# DisplayPort_Mux.net
KiCad netlist of a schematic drawn in Altium Designer
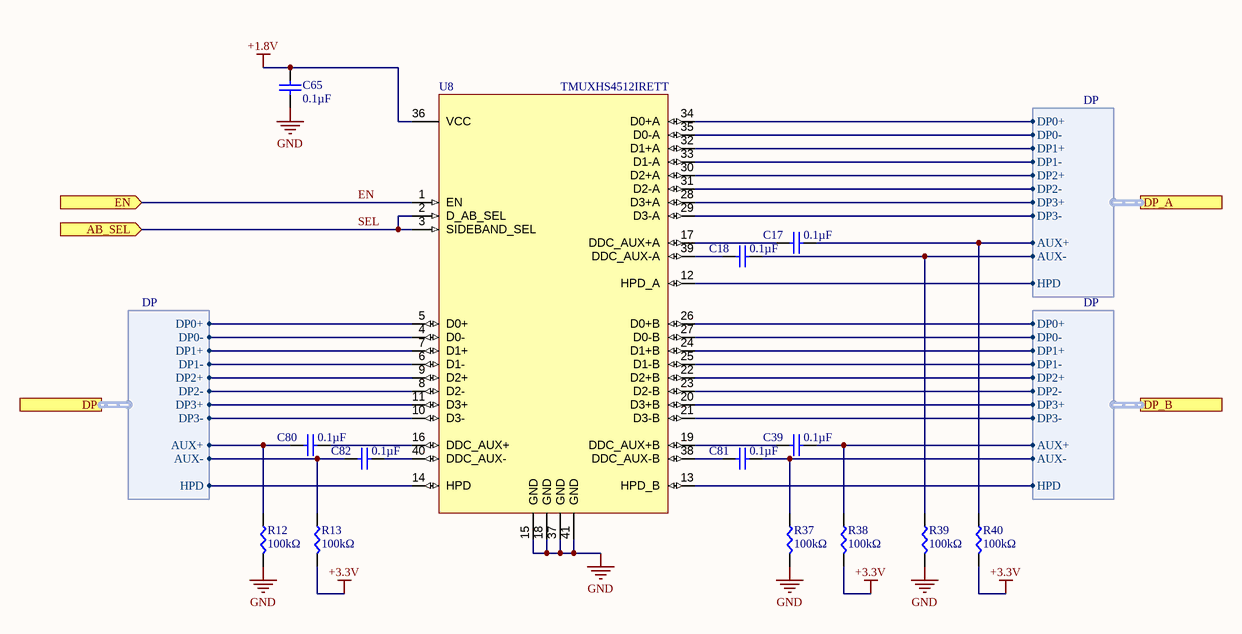
[diagram p0: DisplayPort_Mux.SchDoc]

(export (version "E")
  (design (tool "Eeschema 10.0.6"))
  (components
    (comp (ref "C17")
      (value "0.1µF")
      (footprint "CAP0402")
      (description "0.1 µF ±10% 50V Ceramic Capacitor X5R 0402 (1005 Metric)")
      (fields (field (name "VOLTAGE") "50V") (field (name "Comment") "CC0402KRX5R9BB104"))
      (libsource (lib "Schlib1") (part "CC0402KRX5R9BB104"))
    )
    (comp (ref "C18")
      (value "0.1µF")
      (footprint "CAP0402")
      (description "0.1 µF ±10% 50V Ceramic Capacitor X5R 0402 (1005 Metric)")
      (fields (field (name "VOLTAGE") "50V") (field (name "Comment") "CC0402KRX5R9BB104"))
      (libsource (lib "Schlib1") (part "CC0402KRX5R9BB104"))
    )
    (comp (ref "C39")
      (value "0.1µF")
      (footprint "CAP0402")
      (description "0.1 µF ±10% 50V Ceramic Capacitor X5R 0402 (1005 Metric)")
      (fields (field (name "VOLTAGE") "50V") (field (name "Comment") "CC0402KRX5R9BB104"))
      (libsource (lib "Schlib1") (part "CC0402KRX5R9BB104"))
    )
    (comp (ref "C65")
      (value "0.1µF")
      (footprint "CAP0402")
      (description "0.1 µF ±10% 50V Ceramic Capacitor X5R 0402 (1005 Metric)")
      (fields (field (name "VOLTAGE") "50V") (field (name "Comment") "CC0402KRX5R9BB104"))
      (libsource (lib "Schlib1") (part "CC0402KRX5R9BB104"))
    )
    (comp (ref "C80")
      (value "0.1µF")
      (footprint "CAP0402")
      (description "0.1 µF ±10% 50V Ceramic Capacitor X5R 0402 (1005 Metric)")
      (fields (field (name "VOLTAGE") "50V") (field (name "Comment") "CC0402KRX5R9BB104"))
      (libsource (lib "Schlib1") (part "CC0402KRX5R9BB104"))
    )
    (comp (ref "C81")
      (value "0.1µF")
      (footprint "CAP0402")
      (description "0.1 µF ±10% 50V Ceramic Capacitor X5R 0402 (1005 Metric)")
      (fields (field (name "VOLTAGE") "50V") (field (name "Comment") "CC0402KRX5R9BB104"))
      (libsource (lib "Schlib1") (part "CC0402KRX5R9BB104"))
    )
    (comp (ref "C82")
      (value "0.1µF")
      (footprint "CAP0402")
      (description "0.1 µF ±10% 50V Ceramic Capacitor X5R 0402 (1005 Metric)")
      (fields (field (name "VOLTAGE") "50V") (field (name "Comment") "CC0402KRX5R9BB104"))
      (libsource (lib "Schlib1") (part "CC0402KRX5R9BB104"))
    )
    (comp (ref "R12")
      (value "100kΩ")
      (footprint "RES0402")
      (description "100 kOhms ±1% 0.1W, 1/10W Chip Resistor 0402 (1005 Metric) Automotive AEC-Q200 Thick Film")
      (fields (field (name "Comment") "ERJ-2RKF1003X"))
      (libsource (lib "Schlib1") (part "ERJ-2RKF1003X"))
    )
    (comp (ref "R13")
      (value "100kΩ")
      (footprint "RES0402")
      (description "100 kOhms ±1% 0.1W, 1/10W Chip Resistor 0402 (1005 Metric) Automotive AEC-Q200 Thick Film")
      (fields (field (name "Comment") "ERJ-2RKF1003X"))
      (libsource (lib "Schlib1") (part "ERJ-2RKF1003X"))
    )
    (comp (ref "R37")
      (value "100kΩ")
      (footprint "RES0402")
      (description "100 kOhms ±1% 0.1W, 1/10W Chip Resistor 0402 (1005 Metric) Automotive AEC-Q200 Thick Film")
      (fields (field (name "Comment") "ERJ-2RKF1003X"))
      (libsource (lib "Schlib1") (part "ERJ-2RKF1003X"))
    )
    (comp (ref "R38")
      (value "100kΩ")
      (footprint "RES0402")
      (description "100 kOhms ±1% 0.1W, 1/10W Chip Resistor 0402 (1005 Metric) Automotive AEC-Q200 Thick Film")
      (fields (field (name "Comment") "ERJ-2RKF1003X"))
      (libsource (lib "Schlib1") (part "ERJ-2RKF1003X"))
    )
    (comp (ref "R39")
      (value "100kΩ")
      (footprint "RES0402")
      (description "100 kOhms ±1% 0.1W, 1/10W Chip Resistor 0402 (1005 Metric) Automotive AEC-Q200 Thick Film")
      (fields (field (name "Comment") "ERJ-2RKF1003X"))
      (libsource (lib "Schlib1") (part "ERJ-2RKF1003X"))
    )
    (comp (ref "R40")
      (value "100kΩ")
      (footprint "RES0402")
      (description "100 kOhms ±1% 0.1W, 1/10W Chip Resistor 0402 (1005 Metric) Automotive AEC-Q200 Thick Film")
      (fields (field (name "Comment") "ERJ-2RKF1003X"))
      (libsource (lib "Schlib1") (part "ERJ-2RKF1003X"))
    )
    (comp (ref "U8")
      (value "TMUXHS4512IRETT")
      (description "6 Circuit IC Switch 1:2, 2:1 160Ohm 40-WQFN (6x3)")
      (fields (field (name "MANUFACTURER") "Texas Instruments"))
      (libsource (lib "Schlib1") (part "TMUXHS4512IRETT"))
    )
  )
  (nets
    (net (code "2") (name "+1.8V") (class "Default")
      (node (ref "C65") (pin "2") (pinfunction "2_2") (pintype "passive"))
      (node (ref "U8") (pin "36") (pinfunction "VCC_36") (pintype "passive"))
    )
    (net (code "3") (name "+3.3V") (class "Default")
      (node (ref "R13") (pin "1") (pinfunction "1_1") (pintype "passive"))
      (node (ref "R38") (pin "1") (pinfunction "1_1") (pintype "passive"))
      (node (ref "R40") (pin "1") (pinfunction "1_1") (pintype "passive"))
    )
    (net (code "4") (name "/EN") (class "Default")
      (node (ref "U8") (pin "1") (pinfunction "EN_1") (pintype "input"))
    )
    (net (code "5") (name "/SEL") (class "Default")
      (node (ref "U8") (pin "2") (pinfunction "D_AB_SEL_2") (pintype "input"))
      (node (ref "U8") (pin "3") (pinfunction "SIDEBAND_SEL_3") (pintype "input"))
    )
    (net (code "7") (name "GND") (class "Default")
      (node (ref "C65") (pin "1") (pinfunction "1_1") (pintype "passive"))
      (node (ref "R12") (pin "1") (pinfunction "1_1") (pintype "passive"))
      (node (ref "R37") (pin "1") (pinfunction "1_1") (pintype "passive"))
      (node (ref "R39") (pin "1") (pinfunction "1_1") (pintype "passive"))
      (node (ref "U8") (pin "15") (pinfunction "GND_15") (pintype "passive"))
      (node (ref "U8") (pin "18") (pinfunction "GND_18") (pintype "passive"))
      (node (ref "U8") (pin "37") (pinfunction "GND_37") (pintype "passive"))
      (node (ref "U8") (pin "41") (pinfunction "GND_41") (pintype "passive"))
    )
    (net (code "8") (name "Net-(C17-Pad2)") (class "Default")
      (node (ref "C17") (pin "2") (pinfunction "2_2") (pintype "passive"))
      (node (ref "R40") (pin "2") (pinfunction "2_2") (pintype "passive"))
    )
    (net (code "9") (name "Net-(C18-Pad2)") (class "Default")
      (node (ref "C18") (pin "2") (pinfunction "2_2") (pintype "passive"))
      (node (ref "R39") (pin "2") (pinfunction "2_2") (pintype "passive"))
    )
    (net (code "10") (name "Net-(C39-Pad2)") (class "Default")
      (node (ref "C39") (pin "2") (pinfunction "2_2") (pintype "passive"))
      (node (ref "R38") (pin "2") (pinfunction "2_2") (pintype "passive"))
    )
    (net (code "11") (name "Net-(C80-Pad1)") (class "Default")
      (node (ref "C80") (pin "1") (pinfunction "1_1") (pintype "passive"))
      (node (ref "R12") (pin "2") (pinfunction "2_2") (pintype "passive"))
    )
    (net (code "12") (name "Net-(C81-Pad2)") (class "Default")
      (node (ref "C81") (pin "2") (pinfunction "2_2") (pintype "passive"))
      (node (ref "R37") (pin "2") (pinfunction "2_2") (pintype "passive"))
    )
    (net (code "13") (name "Net-(C82-Pad1)") (class "Default")
      (node (ref "C82") (pin "1") (pinfunction "1_1") (pintype "passive"))
      (node (ref "R13") (pin "2") (pinfunction "2_2") (pintype "passive"))
    )
    (net (code "14") (name "Net-(U8-DDC_AUX+)") (class "Default")
      (node (ref "C80") (pin "2") (pinfunction "2_2") (pintype "passive"))
      (node (ref "U8") (pin "16") (pinfunction "DDC_AUX+_16") (pintype "bidirectional"))
    )
    (net (code "15") (name "Net-(U8-DDC_AUX+A)") (class "Default")
      (node (ref "C17") (pin "1") (pinfunction "1_1") (pintype "passive"))
      (node (ref "U8") (pin "17") (pinfunction "DDC_AUX+A_17") (pintype "bidirectional"))
    )
    (net (code "16") (name "Net-(U8-DDC_AUX+B)") (class "Default")
      (node (ref "C39") (pin "1") (pinfunction "1_1") (pintype "passive"))
      (node (ref "U8") (pin "19") (pinfunction "DDC_AUX+B_19") (pintype "bidirectional"))
    )
    (net (code "17") (name "Net-(U8-DDC_AUX-)") (class "Default")
      (node (ref "C82") (pin "2") (pinfunction "2_2") (pintype "passive"))
      (node (ref "U8") (pin "40") (pinfunction "DDC_AUX-_40") (pintype "bidirectional"))
    )
    (net (code "18") (name "Net-(U8-DDC_AUX-A)") (class "Default")
      (node (ref "C18") (pin "1") (pinfunction "1_1") (pintype "passive"))
      (node (ref "U8") (pin "39") (pinfunction "DDC_AUX-A_39") (pintype "bidirectional"))
    )
    (net (code "19") (name "Net-(U8-DDC_AUX-B)") (class "Default")
      (node (ref "C81") (pin "1") (pinfunction "1_1") (pintype "passive"))
      (node (ref "U8") (pin "38") (pinfunction "DDC_AUX-B_38") (pintype "bidirectional"))
    )
    (net (code "20") (name "unconnected-(U8-D0+-Pad5)") (class "Default")
      (node (ref "U8") (pin "5") (pinfunction "D0+_5") (pintype "bidirectional"))
    )
    (net (code "21") (name "unconnected-(U8-D0+A-Pad34)") (class "Default")
      (node (ref "U8") (pin "34") (pinfunction "D0+A_34") (pintype "bidirectional"))
    )
    (net (code "22") (name "unconnected-(U8-D0+B-Pad26)") (class "Default")
      (node (ref "U8") (pin "26") (pinfunction "D0+B_26") (pintype "bidirectional"))
    )
    (net (code "23") (name "unconnected-(U8-D0--Pad4)") (class "Default")
      (node (ref "U8") (pin "4") (pinfunction "D0-_4") (pintype "bidirectional"))
    )
    (net (code "24") (name "unconnected-(U8-D0-A-Pad35)") (class "Default")
      (node (ref "U8") (pin "35") (pinfunction "D0-A_35") (pintype "bidirectional"))
    )
    (net (code "25") (name "unconnected-(U8-D0-B-Pad27)") (class "Default")
      (node (ref "U8") (pin "27") (pinfunction "D0-B_27") (pintype "bidirectional"))
    )
    (net (code "26") (name "unconnected-(U8-D1+-Pad7)") (class "Default")
      (node (ref "U8") (pin "7") (pinfunction "D1+_7") (pintype "bidirectional"))
    )
    (net (code "27") (name "unconnected-(U8-D1+A-Pad32)") (class "Default")
      (node (ref "U8") (pin "32") (pinfunction "D1+A_32") (pintype "bidirectional"))
    )
    (net (code "28") (name "unconnected-(U8-D1+B-Pad24)") (class "Default")
      (node (ref "U8") (pin "24") (pinfunction "D1+B_24") (pintype "bidirectional"))
    )
    (net (code "29") (name "unconnected-(U8-D1--Pad6)") (class "Default")
      (node (ref "U8") (pin "6") (pinfunction "D1-_6") (pintype "bidirectional"))
    )
    (net (code "30") (name "unconnected-(U8-D1-A-Pad33)") (class "Default")
      (node (ref "U8") (pin "33") (pinfunction "D1-A_33") (pintype "bidirectional"))
    )
    (net (code "31") (name "unconnected-(U8-D1-B-Pad25)") (class "Default")
      (node (ref "U8") (pin "25") (pinfunction "D1-B_25") (pintype "bidirectional"))
    )
    (net (code "32") (name "unconnected-(U8-D2+-Pad9)") (class "Default")
      (node (ref "U8") (pin "9") (pinfunction "D2+_9") (pintype "bidirectional"))
    )
    (net (code "33") (name "unconnected-(U8-D2+A-Pad30)") (class "Default")
      (node (ref "U8") (pin "30") (pinfunction "D2+A_30") (pintype "bidirectional"))
    )
    (net (code "34") (name "unconnected-(U8-D2+B-Pad22)") (class "Default")
      (node (ref "U8") (pin "22") (pinfunction "D2+B_22") (pintype "bidirectional"))
    )
    (net (code "35") (name "unconnected-(U8-D2--Pad8)") (class "Default")
      (node (ref "U8") (pin "8") (pinfunction "D2-_8") (pintype "bidirectional"))
    )
    (net (code "36") (name "unconnected-(U8-D2-A-Pad31)") (class "Default")
      (node (ref "U8") (pin "31") (pinfunction "D2-A_31") (pintype "bidirectional"))
    )
    (net (code "37") (name "unconnected-(U8-D2-B-Pad23)") (class "Default")
      (node (ref "U8") (pin "23") (pinfunction "D2-B_23") (pintype "bidirectional"))
    )
    (net (code "38") (name "unconnected-(U8-D3+-Pad11)") (class "Default")
      (node (ref "U8") (pin "11") (pinfunction "D3+_11") (pintype "bidirectional"))
    )
    (net (code "39") (name "unconnected-(U8-D3+A-Pad28)") (class "Default")
      (node (ref "U8") (pin "28") (pinfunction "D3+A_28") (pintype "bidirectional"))
    )
    (net (code "40") (name "unconnected-(U8-D3+B-Pad20)") (class "Default")
      (node (ref "U8") (pin "20") (pinfunction "D3+B_20") (pintype "bidirectional"))
    )
    (net (code "41") (name "unconnected-(U8-D3--Pad10)") (class "Default")
      (node (ref "U8") (pin "10") (pinfunction "D3-_10") (pintype "bidirectional"))
    )
    (net (code "42") (name "unconnected-(U8-D3-A-Pad29)") (class "Default")
      (node (ref "U8") (pin "29") (pinfunction "D3-A_29") (pintype "bidirectional"))
    )
    (net (code "43") (name "unconnected-(U8-D3-B-Pad21)") (class "Default")
      (node (ref "U8") (pin "21") (pinfunction "D3-B_21") (pintype "bidirectional"))
    )
    (net (code "44") (name "unconnected-(U8-HPD-Pad14)") (class "Default")
      (node (ref "U8") (pin "14") (pinfunction "HPD_14") (pintype "bidirectional"))
    )
    (net (code "45") (name "unconnected-(U8-HPD_A-Pad12)") (class "Default")
      (node (ref "U8") (pin "12") (pinfunction "HPD_A_12") (pintype "bidirectional"))
    )
    (net (code "46") (name "unconnected-(U8-HPD_B-Pad13)") (class "Default")
      (node (ref "U8") (pin "13") (pinfunction "HPD_B_13") (pintype "bidirectional"))
    )
  )
)
